# openSX70_chocolate_V34_20180103_manually.net
KiCad netlist of a schematic drawn in EAGLE
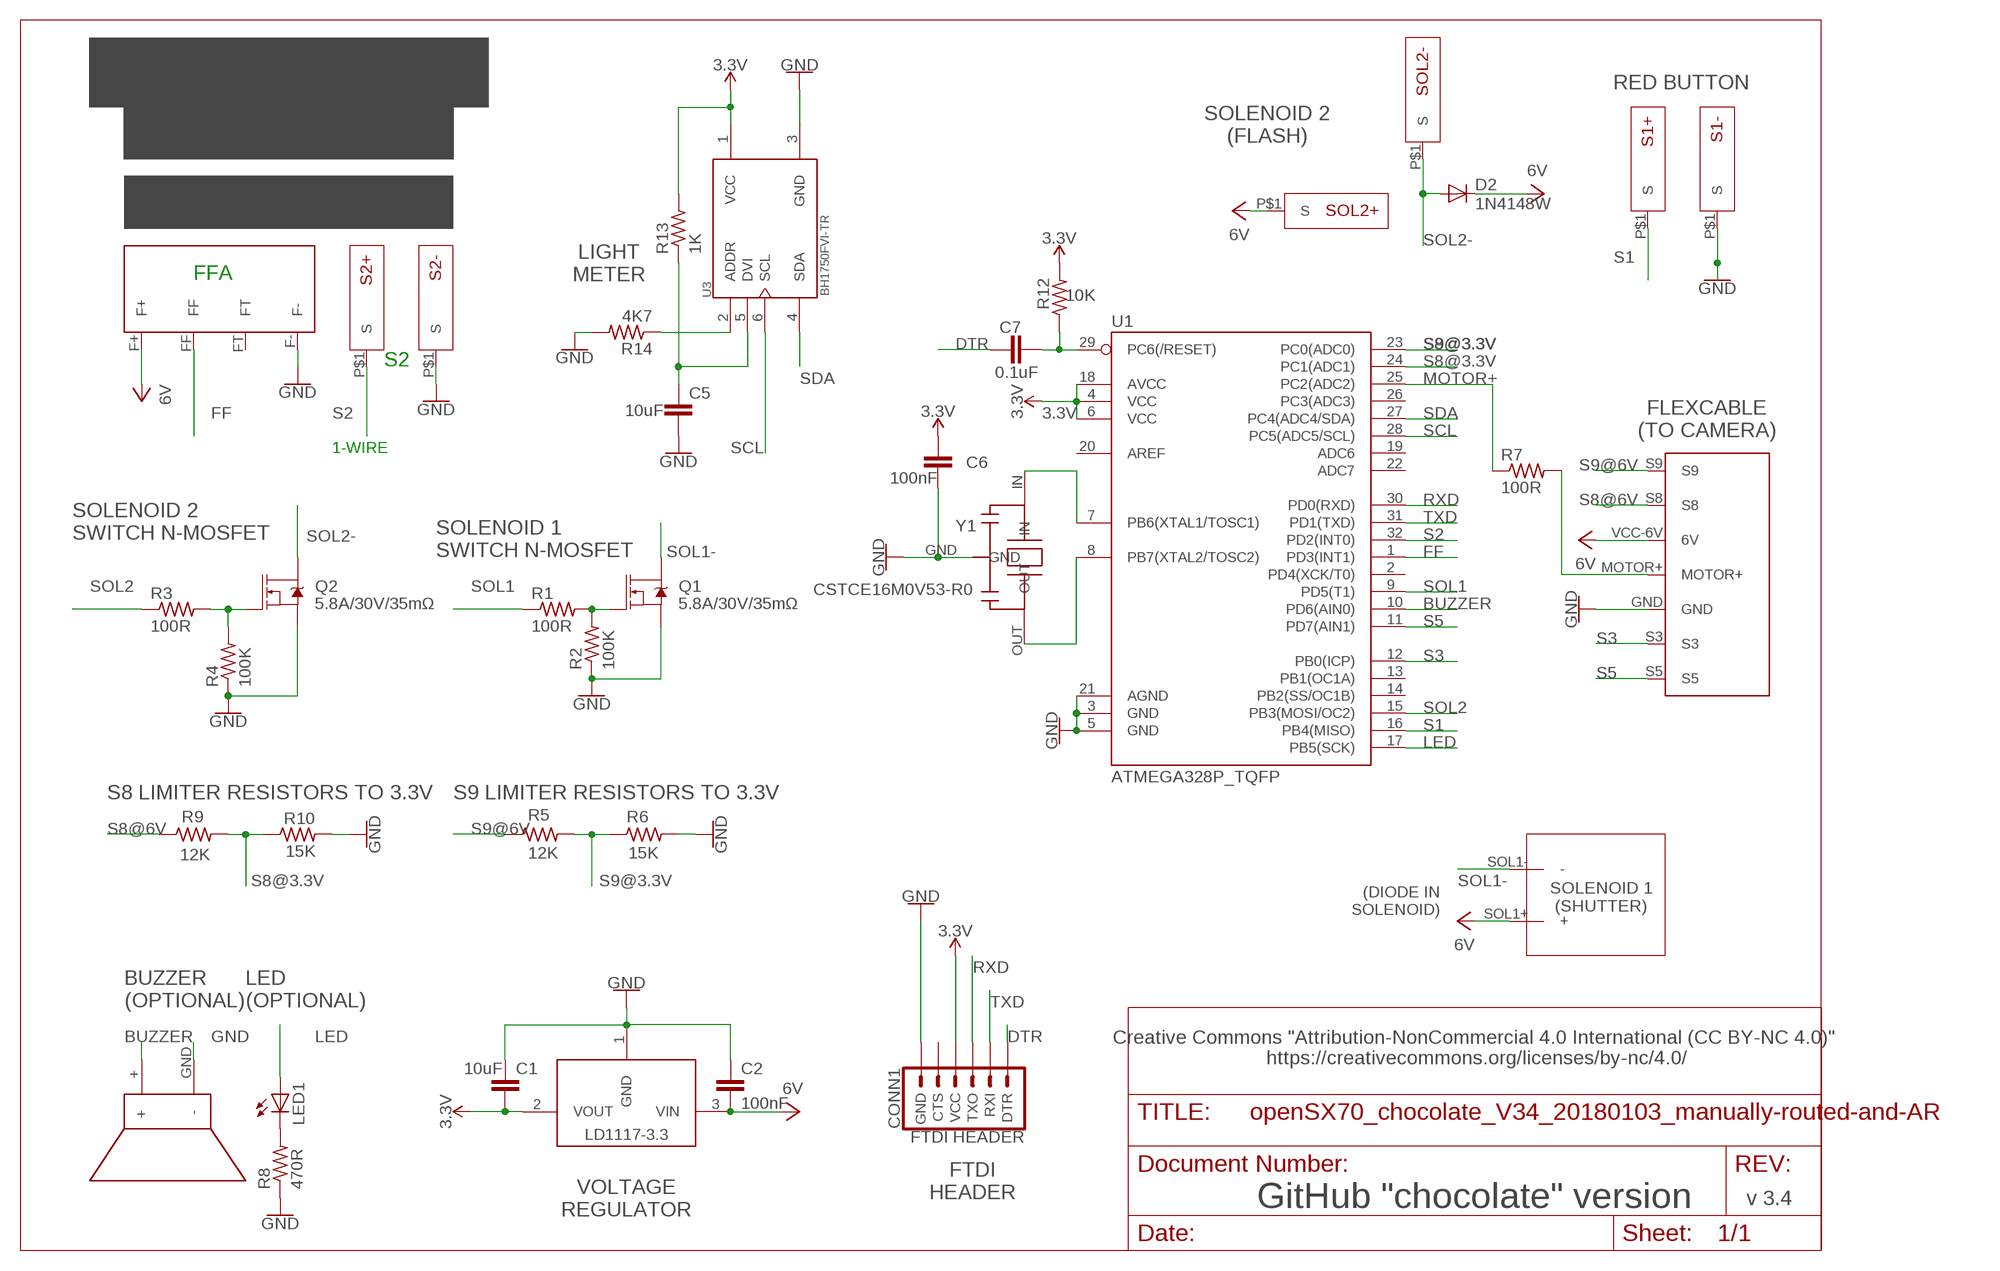
[diagram p0: schematic, sheet 1]

(export (version "E")
  (design (tool "Eeschema 10.0.6"))
  (components
    (comp (ref "BUZZ1")
      (value "CSET8-5G")
      (footprint "eagle-import:CSET8-5G_PACKAGE")
      (libsource (lib "eagle-import") (part "CSET8-5G"))
    )
    (comp (ref "C1")
      (value "10uF")
      (footprint "eagle-import:0603")
      (libsource (lib "eagle-import") (part "10UF-0603-6.3V-20%"))
    )
    (comp (ref "C2")
      (value "100nF")
      (footprint "eagle-import:C0603K")
      (libsource (lib "eagle-import") (part "C-EUC0603K"))
    )
    (comp (ref "C5")
      (value "10uF")
      (footprint "eagle-import:0603")
      (libsource (lib "eagle-import") (part "10UF-0603-6.3V-20%"))
    )
    (comp (ref "C6")
      (value "100nF")
      (footprint "eagle-import:C0805")
      (libsource (lib "eagle-import") (part "resistor_C-EUC0805"))
    )
    (comp (ref "C7")
      (value "0.1uF")
      (footprint "eagle-import:0603")
      (libsource (lib "eagle-import") (part "0.1UF-0603-25V-(+80/-20%)"))
    )
    (comp (ref "CONN1")
      (value "FTDI HEADER")
      (footprint "eagle-import:1X06")
      (libsource (lib "eagle-import") (part "6_PIN_SERIAL_TARGET"))
    )
    (comp (ref "D2")
      (value "1N4148W")
      (footprint "eagle-import:SOD-123_MINI-SMA")
      (libsource (lib "eagle-import") (part "CGRM400-G1"))
    )
    (comp (ref "LD11173.3V")
      (value "LD1117 3.3V")
      (footprint "eagle-import:SOT223")
      (fields (field (name "MF") "Advanced Monolithic Systems") (field (name "MP") "AMS1117-5.0"))
      (libsource (lib "eagle-import") (part "LD1117-3.3"))
    )
    (comp (ref "LED1")
      (value "LEDCHIPLED_0805")
      (footprint "eagle-import:CHIPLED_0805")
      (libsource (lib "eagle-import") (part "LEDCHIPLED_0805"))
    )
    (comp (ref "Q1")
      (value "5.8A/30V/35mΩ")
      (footprint "eagle-import:SOT23-3")
      (libsource (lib "eagle-import") (part "MOSFET-NCH-AO3404A"))
    )
    (comp (ref "Q2")
      (value "5.8A/30V/35mΩ")
      (footprint "eagle-import:SOT23-3")
      (libsource (lib "eagle-import") (part "MOSFET-NCH-AO3404A"))
    )
    (comp (ref "R1")
      (value "100R")
      (footprint "eagle-import:R0603")
      (libsource (lib "eagle-import") (part "R-US_R0603"))
    )
    (comp (ref "R2")
      (value "100K")
      (footprint "eagle-import:R0603")
      (libsource (lib "eagle-import") (part "R-US_R0603"))
    )
    (comp (ref "R3")
      (value "100R")
      (footprint "eagle-import:R0603")
      (libsource (lib "eagle-import") (part "R-US_R0603"))
    )
    (comp (ref "R4")
      (value "100K")
      (footprint "eagle-import:R0603")
      (libsource (lib "eagle-import") (part "R-US_R0603"))
    )
    (comp (ref "R5")
      (value "12K")
      (footprint "eagle-import:R0603")
      (libsource (lib "eagle-import") (part "R-US_R0603"))
    )
    (comp (ref "R6")
      (value "15K")
      (footprint "eagle-import:R0603")
      (libsource (lib "eagle-import") (part "R-US_R0603"))
    )
    (comp (ref "R7")
      (value "100R")
      (footprint "eagle-import:R0603")
      (libsource (lib "eagle-import") (part "R-US_R0603"))
    )
    (comp (ref "R8")
      (value "470R")
      (footprint "eagle-import:R0603")
      (libsource (lib "eagle-import") (part "R-US_R0603"))
    )
    (comp (ref "R9")
      (value "12K")
      (footprint "eagle-import:R0603")
      (libsource (lib "eagle-import") (part "R-US_R0603"))
    )
    (comp (ref "R10")
      (value "15K")
      (footprint "eagle-import:R0603")
      (libsource (lib "eagle-import") (part "R-US_R0603"))
    )
    (comp (ref "R12")
      (value "10K")
      (footprint "eagle-import:R0603")
      (libsource (lib "eagle-import") (part "R-US_R0603"))
    )
    (comp (ref "R13")
      (value "1K")
      (footprint "eagle-import:R0603")
      (libsource (lib "eagle-import") (part "R-US_R0603"))
    )
    (comp (ref "R14")
      (value "4K7")
      (footprint "eagle-import:R0603")
      (libsource (lib "eagle-import") (part "R-US_R0603"))
    )
    (comp (ref "S1+")
      (value "SX70-S-PAD-NEW")
      (footprint "eagle-import:SX70-S-PAD2")
      (libsource (lib "eagle-import") (part "SX70-S-PAD-NEW"))
    )
    (comp (ref "S1-")
      (value "SX70-S-PAD-NEW")
      (footprint "eagle-import:SX70-S-PAD2")
      (libsource (lib "eagle-import") (part "SX70-S-PAD-NEW"))
    )
    (comp (ref "S2+")
      (value "SX70-S-PAD-NEW")
      (footprint "eagle-import:SX70-S-PAD2")
      (libsource (lib "eagle-import") (part "SX70-S-PAD-NEW"))
    )
    (comp (ref "S2-")
      (value "SX70-S-PAD-NEW")
      (footprint "eagle-import:SX70-S-PAD2")
      (libsource (lib "eagle-import") (part "SX70-S-PAD-NEW"))
    )
    (comp (ref "SOL1")
      (value "SX70-SOLENOID1-2PADS")
      (footprint "eagle-import:SX70-SOLENOID1-2")
      (libsource (lib "eagle-import") (part "SX70-SOLENOID1-2PADS"))
    )
    (comp (ref "SOL2+")
      (value "SX70-S-PAD-NEW")
      (footprint "eagle-import:SX70-S-PAD2")
      (libsource (lib "eagle-import") (part "SX70-S-PAD-NEW"))
    )
    (comp (ref "SOL2-")
      (value "SX70-S-PAD-NEW")
      (footprint "eagle-import:SX70-S-PAD2")
      (libsource (lib "eagle-import") (part "SX70-S-PAD-NEW"))
    )
    (comp (ref "U$1")
      (value "SX70-7-PAD")
      (footprint "eagle-import:SX70-7-PAD")
      (libsource (lib "eagle-import") (part "SX70-7-PAD"))
    )
    (comp (ref "U$2")
      (value "FFA")
      (footprint "eagle-import:FFA-PAD-PACKAGE")
      (libsource (lib "eagle-import") (part "SX70-FFA-PAD"))
    )
    (comp (ref "U1")
      (value "ATMEGA328P_TQFP")
      (footprint "eagle-import:TQFP32-08")
      (libsource (lib "eagle-import") (part "ATMEGA328P_TQFP"))
    )
    (comp (ref "U3")
      (value "BH1750FVI-TR")
      (footprint "eagle-import:SOTFL50P300X75-6N")
      (fields (field (name "MF") "Rohm"))
      (libsource (lib "eagle-import") (part "BH1750FVI-TR"))
    )
    (comp (ref "Y1")
      (value "CSTCE16M0V53-R0")
      (footprint "eagle-import:CFP95P160X100-3N")
      (fields (field (name "MF") "Murata"))
      (libsource (lib "eagle-import") (part "CSTCE16M0V53-R0"))
    )
  )
  (nets
    (net (code "1") (name "/BUZZER") (class "Default")
      (node (ref "BUZZ1") (pin "+") (pinfunction "+_+") (pintype "bidirectional"))
      (node (ref "U1") (pin "10") (pinfunction "PD6(AIN0)_10") (pintype "bidirectional"))
    )
    (net (code "2") (name "/DTR") (class "Default")
      (node (ref "C7") (pin "1") (pinfunction "1_1") (pintype "passive"))
      (node (ref "CONN1") (pin "1") (pinfunction "DTR_1") (pintype "passive"))
    )
    (net (code "3") (name "/FF") (class "Default")
      (node (ref "U$2") (pin "FF") (pinfunction "FF_FF") (pintype "bidirectional"))
      (node (ref "U1") (pin "1") (pinfunction "PD3(INT1)_1") (pintype "bidirectional"))
    )
    (net (code "4") (name "/LED") (class "Default")
      (node (ref "LED1") (pin "A") (pinfunction "A_A") (pintype "passive"))
      (node (ref "U1") (pin "17") (pinfunction "PB5(SCK)_17") (pintype "bidirectional"))
    )
    (net (code "5") (name "/MOTOR+") (class "Default")
      (node (ref "R7") (pin "1") (pinfunction "1_1") (pintype "passive"))
      (node (ref "U1") (pin "25") (pinfunction "PC2(ADC2)_25") (pintype "bidirectional"))
    )
    (net (code "6") (name "/RXD") (class "Default")
      (node (ref "CONN1") (pin "3") (pinfunction "TXO_3") (pintype "passive"))
      (node (ref "U1") (pin "30") (pinfunction "PD0(RXD)_30") (pintype "bidirectional"))
    )
    (net (code "7") (name "/S1") (class "Default")
      (node (ref "S1+") (pin "P$1") (pinfunction "S_P$1") (pintype "bidirectional"))
      (node (ref "U1") (pin "16") (pinfunction "PB4(MISO)_16") (pintype "bidirectional"))
    )
    (net (code "8") (name "/S2") (class "Default")
      (node (ref "S2+") (pin "P$1") (pinfunction "S_P$1") (pintype "bidirectional"))
      (node (ref "U1") (pin "32") (pinfunction "PD2(INT0)_32") (pintype "bidirectional"))
    )
    (net (code "9") (name "/S3") (class "Default")
      (node (ref "U$1") (pin "S3") (pinfunction "S3_S3") (pintype "bidirectional"))
      (node (ref "U1") (pin "12") (pinfunction "PB0(ICP)_12") (pintype "bidirectional"))
    )
    (net (code "10") (name "/S5") (class "Default")
      (node (ref "U$1") (pin "S5") (pinfunction "S5_S5") (pintype "bidirectional"))
      (node (ref "U1") (pin "11") (pinfunction "PD7(AIN1)_11") (pintype "bidirectional"))
    )
    (net (code "11") (name "/S8@3.3V") (class "Default")
      (node (ref "R10") (pin "1") (pinfunction "1_1") (pintype "passive"))
      (node (ref "R9") (pin "2") (pinfunction "2_2") (pintype "passive"))
      (node (ref "U1") (pin "24") (pinfunction "PC1(ADC1)_24") (pintype "bidirectional"))
    )
    (net (code "12") (name "/S8@6V") (class "Default")
      (node (ref "R9") (pin "1") (pinfunction "1_1") (pintype "passive"))
      (node (ref "U$1") (pin "S8") (pinfunction "S8_S8") (pintype "bidirectional"))
    )
    (net (code "13") (name "/S9@3.3V") (class "Default")
      (node (ref "R5") (pin "2") (pinfunction "2_2") (pintype "passive"))
      (node (ref "R6") (pin "1") (pinfunction "1_1") (pintype "passive"))
      (node (ref "U1") (pin "23") (pinfunction "PC0(ADC0)_23") (pintype "bidirectional"))
    )
    (net (code "14") (name "/S9@6V") (class "Default")
      (node (ref "R5") (pin "1") (pinfunction "1_1") (pintype "passive"))
      (node (ref "U$1") (pin "S9") (pinfunction "S9_S9") (pintype "bidirectional"))
    )
    (net (code "15") (name "/SCL") (class "Default")
      (node (ref "U1") (pin "28") (pinfunction "PC5(ADC5/SCL)_28") (pintype "bidirectional"))
      (node (ref "U3") (pin "6") (pinfunction "SCL_6") (pintype "input"))
    )
    (net (code "16") (name "/SDA") (class "Default")
      (node (ref "U1") (pin "27") (pinfunction "PC4(ADC4/SDA)_27") (pintype "bidirectional"))
      (node (ref "U3") (pin "4") (pinfunction "SDA_4") (pintype "bidirectional"))
    )
    (net (code "17") (name "/SOL1") (class "Default")
      (node (ref "R1") (pin "1") (pinfunction "1_1") (pintype "passive"))
      (node (ref "U1") (pin "9") (pinfunction "PD5(T1)_9") (pintype "bidirectional"))
    )
    (net (code "18") (name "/SOL1-") (class "Default")
      (node (ref "Q1") (pin "3") (pinfunction "D_3") (pintype "bidirectional"))
      (node (ref "SOL1") (pin "SOL1-") (pinfunction "-_SOL1-") (pintype "bidirectional"))
    )
    (net (code "19") (name "/SOL2") (class "Default")
      (node (ref "R3") (pin "1") (pinfunction "1_1") (pintype "passive"))
      (node (ref "U1") (pin "15") (pinfunction "PB3(MOSI/OC2)_15") (pintype "bidirectional"))
    )
    (net (code "20") (name "/SOL2-") (class "Default")
      (node (ref "D2") (pin "A") (pinfunction "A_A") (pintype "passive"))
      (node (ref "Q2") (pin "3") (pinfunction "D_3") (pintype "bidirectional"))
      (node (ref "SOL2-") (pin "P$1") (pinfunction "S_P$1") (pintype "bidirectional"))
    )
    (net (code "21") (name "/TXD") (class "Default")
      (node (ref "CONN1") (pin "2") (pinfunction "RXI_2") (pintype "passive"))
      (node (ref "U1") (pin "31") (pinfunction "PD1(TXD)_31") (pintype "bidirectional"))
    )
    (net (code "22") (name "3.3V") (class "Default")
      (node (ref "C1") (pin "2") (pinfunction "2_2") (pintype "passive"))
      (node (ref "C6") (pin "1") (pinfunction "1_1") (pintype "passive"))
      (node (ref "CONN1") (pin "4") (pinfunction "VCC_4") (pintype "passive"))
      (node (ref "LD11173.3V") (pin "2") (pinfunction "VOUT_2") (pintype "bidirectional"))
      (node (ref "R12") (pin "2") (pinfunction "2_2") (pintype "passive"))
      (node (ref "R13") (pin "2") (pinfunction "2_2") (pintype "passive"))
      (node (ref "U1") (pin "18") (pinfunction "AVCC_18") (pintype "bidirectional"))
      (node (ref "U1") (pin "4") (pinfunction "VCC_4") (pintype "bidirectional"))
      (node (ref "U1") (pin "6") (pinfunction "VCC_6") (pintype "bidirectional"))
      (node (ref "U3") (pin "1") (pinfunction "VCC_1") (pintype "power_in"))
    )
    (net (code "23") (name "6V") (class "Default")
      (node (ref "C2") (pin "2") (pinfunction "2_2") (pintype "passive"))
      (node (ref "D2") (pin "C") (pinfunction "C_C") (pintype "passive"))
      (node (ref "LD11173.3V") (pin "3") (pinfunction "VIN_3") (pintype "bidirectional"))
      (node (ref "SOL1") (pin "SOL1+") (pinfunction "+_SOL1+") (pintype "bidirectional"))
      (node (ref "SOL2+") (pin "P$1") (pinfunction "S_P$1") (pintype "bidirectional"))
      (node (ref "U$1") (pin "VCC-6V") (pinfunction "6V_VCC-6V") (pintype "bidirectional"))
      (node (ref "U$2") (pin "F+") (pinfunction "F+_F+") (pintype "bidirectional"))
    )
    (net (code "24") (name "GND") (class "Default")
      (node (ref "BUZZ1") (pin "GND") (pinfunction "-_GND") (pintype "bidirectional"))
      (node (ref "C1") (pin "1") (pinfunction "1_1") (pintype "passive"))
      (node (ref "C2") (pin "1") (pinfunction "1_1") (pintype "passive"))
      (node (ref "C5") (pin "2") (pinfunction "2_2") (pintype "passive"))
      (node (ref "C6") (pin "2") (pinfunction "2_2") (pintype "passive"))
      (node (ref "CONN1") (pin "6") (pinfunction "GND_6") (pintype "passive"))
      (node (ref "LD11173.3V") (pin "1") (pinfunction "GND_1") (pintype "bidirectional"))
      (node (ref "Q1") (pin "2") (pinfunction "S_2") (pintype "bidirectional"))
      (node (ref "Q2") (pin "2") (pinfunction "S_2") (pintype "bidirectional"))
      (node (ref "R10") (pin "2") (pinfunction "2_2") (pintype "passive"))
      (node (ref "R14") (pin "2") (pinfunction "2_2") (pintype "passive"))
      (node (ref "R2") (pin "1") (pinfunction "1_1") (pintype "passive"))
      (node (ref "R4") (pin "1") (pinfunction "1_1") (pintype "passive"))
      (node (ref "R6") (pin "2") (pinfunction "2_2") (pintype "passive"))
      (node (ref "R8") (pin "1") (pinfunction "1_1") (pintype "passive"))
      (node (ref "S1-") (pin "P$1") (pinfunction "S_P$1") (pintype "bidirectional"))
      (node (ref "S2-") (pin "P$1") (pinfunction "S_P$1") (pintype "bidirectional"))
      (node (ref "U$1") (pin "GND") (pinfunction "GND_GND") (pintype "bidirectional"))
      (node (ref "U$2") (pin "F-") (pinfunction "F-_F-") (pintype "bidirectional"))
      (node (ref "U1") (pin "21") (pinfunction "AGND_21") (pintype "bidirectional"))
      (node (ref "U1") (pin "3") (pinfunction "GND_3") (pintype "bidirectional"))
      (node (ref "U1") (pin "5") (pinfunction "GND_5") (pintype "bidirectional"))
      (node (ref "U3") (pin "3") (pinfunction "GND_3") (pintype "power_in"))
      (node (ref "Y1") (pin "GND") (pinfunction "GND_GND") (pintype "passive"))
    )
    (net (code "25") (name "Net-(LED1-PadC)") (class "Default")
      (node (ref "LED1") (pin "C") (pinfunction "C_C") (pintype "passive"))
      (node (ref "R8") (pin "2") (pinfunction "2_2") (pintype "passive"))
    )
    (net (code "26") (name "Net-(Q1-G)") (class "Default")
      (node (ref "Q1") (pin "1") (pinfunction "G_1") (pintype "bidirectional"))
      (node (ref "R1") (pin "2") (pinfunction "2_2") (pintype "passive"))
      (node (ref "R2") (pin "2") (pinfunction "2_2") (pintype "passive"))
    )
    (net (code "27") (name "Net-(Q2-G)") (class "Default")
      (node (ref "Q2") (pin "1") (pinfunction "G_1") (pintype "bidirectional"))
      (node (ref "R3") (pin "2") (pinfunction "2_2") (pintype "passive"))
      (node (ref "R4") (pin "2") (pinfunction "2_2") (pintype "passive"))
    )
    (net (code "28") (name "Net-(R7-Pad2)") (class "Default")
      (node (ref "R7") (pin "2") (pinfunction "2_2") (pintype "passive"))
      (node (ref "U$1") (pin "MOTOR+") (pinfunction "MOTOR+_MOTOR+") (pintype "bidirectional"))
    )
    (net (code "29") (name "Net-(U1-PB6(XTAL1{slash}TOSC1))") (class "Default")
      (node (ref "U1") (pin "7") (pinfunction "PB6(XTAL1/TOSC1)_7") (pintype "bidirectional"))
      (node (ref "Y1") (pin "IN") (pinfunction "IN_IN") (pintype "input"))
    )
    (net (code "30") (name "Net-(U1-PB7(XTAL2{slash}TOSC2))") (class "Default")
      (node (ref "U1") (pin "8") (pinfunction "PB7(XTAL2/TOSC2)_8") (pintype "bidirectional"))
      (node (ref "Y1") (pin "OUT") (pinfunction "OUT_OUT") (pintype "output"))
    )
    (net (code "31") (name "Net-(U1-PC6({slash}RESET))") (class "Default")
      (node (ref "C7") (pin "2") (pinfunction "2_2") (pintype "passive"))
      (node (ref "R12") (pin "1") (pinfunction "1_1") (pintype "passive"))
      (node (ref "U1") (pin "29") (pinfunction "PC6(/RESET)_29") (pintype "bidirectional"))
    )
    (net (code "32") (name "Net-(U3-ADDR)") (class "Default")
      (node (ref "R14") (pin "1") (pinfunction "1_1") (pintype "passive"))
      (node (ref "U3") (pin "2") (pinfunction "ADDR_2") (pintype "input"))
    )
    (net (code "33") (name "Net-(U3-DVI)") (class "Default")
      (node (ref "C5") (pin "1") (pinfunction "1_1") (pintype "passive"))
      (node (ref "R13") (pin "1") (pinfunction "1_1") (pintype "passive"))
      (node (ref "U3") (pin "5") (pinfunction "DVI_5") (pintype "input"))
    )
    (net (code "34") (name "unconnected-(CONN1-CTS-Pad5)") (class "Default")
      (node (ref "CONN1") (pin "5") (pinfunction "CTS_5") (pintype "passive"))
    )
    (net (code "35") (name "unconnected-(U$2-PadFT)") (class "Default")
      (node (ref "U$2") (pin "FT") (pinfunction "FT_FT") (pintype "bidirectional"))
    )
    (net (code "36") (name "unconnected-(U1-ADC6-Pad19)") (class "Default")
      (node (ref "U1") (pin "19") (pinfunction "ADC6_19") (pintype "bidirectional"))
    )
    (net (code "37") (name "unconnected-(U1-ADC7-Pad22)") (class "Default")
      (node (ref "U1") (pin "22") (pinfunction "ADC7_22") (pintype "bidirectional"))
    )
    (net (code "38") (name "unconnected-(U1-AREF-Pad20)") (class "Default")
      (node (ref "U1") (pin "20") (pinfunction "AREF_20") (pintype "bidirectional"))
    )
    (net (code "39") (name "unconnected-(U1-PB1(OC1A)-Pad13)") (class "Default")
      (node (ref "U1") (pin "13") (pinfunction "PB1(OC1A)_13") (pintype "bidirectional"))
    )
    (net (code "40") (name "unconnected-(U1-PB2(SS{slash}OC1B)-Pad14)") (class "Default")
      (node (ref "U1") (pin "14") (pinfunction "PB2(SS/OC1B)_14") (pintype "bidirectional"))
    )
    (net (code "41") (name "unconnected-(U1-PC3(ADC3)-Pad26)") (class "Default")
      (node (ref "U1") (pin "26") (pinfunction "PC3(ADC3)_26") (pintype "bidirectional"))
    )
    (net (code "42") (name "unconnected-(U1-PD4(XCK{slash}T0)-Pad2)") (class "Default")
      (node (ref "U1") (pin "2") (pinfunction "PD4(XCK/T0)_2") (pintype "bidirectional"))
    )
  )
)
